# relay_button.net
KiCad netlist of a schematic drawn in Altium Designer
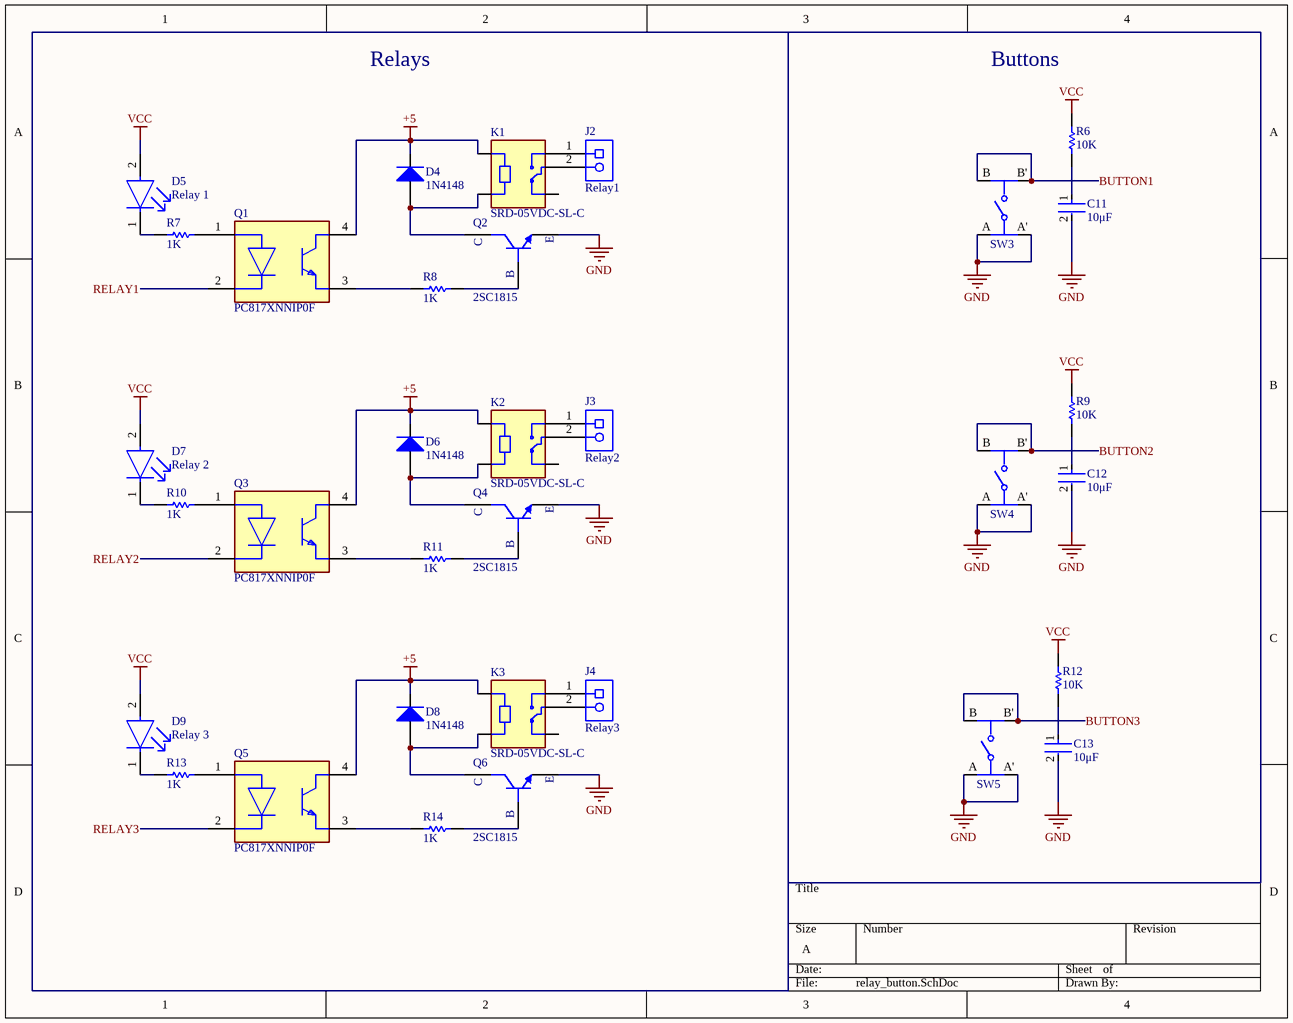
[diagram p0: relay_button.SchDoc]

(export (version "E")
  (design (tool "Eeschema 10.0.6"))
  (components
    (comp (ref "C11")
      (value "10μF")
      (footprint "FP-0603-L_1_6_0_15-W_0_81-IPC_A")
      (description "General Purpose Ceramic Capacitor, 0603, 100nF, 10%, X7R, 15%, 50V")
      (fields (field (name "TOLERANCE") "10%") (field (name "VOLTAGE") "50V"))
      (libsource (lib "Altium Content Vault") (part "02cd4be3c70576c341d710602a673aa"))
    )
    (comp (ref "C12")
      (value "10μF")
      (footprint "FP-0603-L_1_6_0_15-W_0_81-IPC_A")
      (description "General Purpose Ceramic Capacitor, 0603, 100nF, 10%, X7R, 15%, 50V")
      (fields (field (name "TOLERANCE") "10%") (field (name "VOLTAGE") "50V"))
      (libsource (lib "Altium Content Vault") (part "02cd4be3c70576c341d710602a673aa"))
    )
    (comp (ref "C13")
      (value "10μF")
      (footprint "FP-0603-L_1_6_0_15-W_0_81-IPC_A")
      (description "General Purpose Ceramic Capacitor, 0603, 100nF, 10%, X7R, 15%, 50V")
      (fields (field (name "TOLERANCE") "10%") (field (name "VOLTAGE") "50V"))
      (libsource (lib "Altium Content Vault") (part "02cd4be3c70576c341d710602a673aa"))
    )
    (comp (ref "D4")
      (value "1N4148")
      (footprint "NXP-SOD27-2_V")
      (description "High-speed Diode, 100 V, 450 mA, 2-Pin SOD27, RoHS")
      (fields (field (name "MANUFACTURER") "NXP Semiconductors"))
      (libsource (lib "Altium Content Vault") (part "NXP-A1K2-2"))
    )
    (comp (ref "D5")
      (value "Relay 1")
      (footprint "FP-HLMP-4700-MFG")
      (description "LED RED DIFFUSED T-1 3/4 T/H")
      (fields
        (field (name "OCTOPART") "https://octopart.com/hlmp-4700-broadcom-71130526")
        (field (name "MANUFACTURER") "Broadcom")
      )
      (libsource (lib "Altium Content Vault") (part "8706943c75ba83719d021d2fdc84c58"))
    )
    (comp (ref "D6")
      (value "1N4148")
      (footprint "NXP-SOD27-2_V")
      (description "High-speed Diode, 100 V, 450 mA, 2-Pin SOD27, RoHS")
      (fields (field (name "MANUFACTURER") "NXP Semiconductors"))
      (libsource (lib "Altium Content Vault") (part "NXP-A1K2-2"))
    )
    (comp (ref "D7")
      (value "Relay 2")
      (footprint "FP-HLMP-4700-MFG")
      (description "LED RED DIFFUSED T-1 3/4 T/H")
      (fields
        (field (name "OCTOPART") "https://octopart.com/hlmp-4700-broadcom-71130526")
        (field (name "MANUFACTURER") "Broadcom")
      )
      (libsource (lib "Altium Content Vault") (part "8706943c75ba83719d021d2fdc84c58"))
    )
    (comp (ref "D8")
      (value "1N4148")
      (footprint "NXP-SOD27-2_V")
      (description "High-speed Diode, 100 V, 450 mA, 2-Pin SOD27, RoHS")
      (fields (field (name "MANUFACTURER") "NXP Semiconductors"))
      (libsource (lib "Altium Content Vault") (part "NXP-A1K2-2"))
    )
    (comp (ref "D9")
      (value "Relay 3")
      (footprint "FP-HLMP-4700-MFG")
      (description "LED RED DIFFUSED T-1 3/4 T/H")
      (fields
        (field (name "OCTOPART") "https://octopart.com/hlmp-4700-broadcom-71130526")
        (field (name "MANUFACTURER") "Broadcom")
      )
      (libsource (lib "Altium Content Vault") (part "8706943c75ba83719d021d2fdc84c58"))
    )
    (comp (ref "J2")
      (value "Relay1")
      (footprint "PHOE-1729128-2_V")
      (description "PCB Terminal Block, 13.5 A, 400 V, 2-Pin THD, RoHS, Bulk")
      (fields (field (name "PARTNUMBER") "1729128") (field (name "MANUFACTURER") "Phoenix Contact"))
      (libsource (lib "Altium Content Vault") (part "CN-2P-F-R2"))
    )
    (comp (ref "J3")
      (value "Relay2")
      (footprint "PHOE-1729128-2_V")
      (description "PCB Terminal Block, 13.5 A, 400 V, 2-Pin THD, RoHS, Bulk")
      (fields (field (name "PARTNUMBER") "1729128") (field (name "MANUFACTURER") "Phoenix Contact"))
      (libsource (lib "Altium Content Vault") (part "CN-2P-F-R2"))
    )
    (comp (ref "J4")
      (value "Relay3")
      (footprint "PHOE-1729128-2_V")
      (description "PCB Terminal Block, 13.5 A, 400 V, 2-Pin THD, RoHS, Bulk")
      (fields (field (name "PARTNUMBER") "1729128") (field (name "MANUFACTURER") "Phoenix Contact"))
      (libsource (lib "Altium Content Vault") (part "CN-2P-F-R2"))
    )
    (comp (ref "K1")
      (value "SRD-05VDC-SL-C")
      (footprint "RELAY_SRD-05VDC-SL-C")
      (fields (field (name "MF") "{'manufacturer': u'Songle Relay'}"))
      (libsource (lib "SnapEDA_Library") (part "SRD-05VDC-SL-C"))
    )
    (comp (ref "K2")
      (value "SRD-05VDC-SL-C")
      (footprint "RELAY_SRD-05VDC-SL-C")
      (fields (field (name "MF") "{'manufacturer': u'Songle Relay'}"))
      (libsource (lib "SnapEDA_Library") (part "SRD-05VDC-SL-C"))
    )
    (comp (ref "K3")
      (value "SRD-05VDC-SL-C")
      (footprint "RELAY_SRD-05VDC-SL-C")
      (fields (field (name "MF") "{'manufacturer': u'Songle Relay'}"))
      (libsource (lib "SnapEDA_Library") (part "SRD-05VDC-SL-C"))
    )
    (comp (ref "Q1")
      (value "PC817XNNIP0F")
      (footprint "FP-PC817XNNIP0F-MFG")
      (description "OPTOISOLATOR 5KV TRANS 4SMD")
      (libsource (lib "Altium Content Vault") (part "6470904bf6395c62928ee73e60120b8"))
    )
    (comp (ref "Q2")
      (value "2SC1815")
      (footprint "SOT23_3")
      (description "TRANS NPN 50V 0.15A SOT23-3")
      (libsource (lib "BYTECH_HW_LIB_2019") (part "2SC1815"))
    )
    (comp (ref "Q3")
      (value "PC817XNNIP0F")
      (footprint "FP-PC817XNNIP0F-MFG")
      (description "OPTOISOLATOR 5KV TRANS 4SMD")
      (libsource (lib "Altium Content Vault") (part "6470904bf6395c62928ee73e60120b8"))
    )
    (comp (ref "Q4")
      (value "2SC1815")
      (footprint "SOT23_3")
      (description "TRANS NPN 50V 0.15A SOT23-3")
      (libsource (lib "BYTECH_HW_LIB_2019") (part "2SC1815"))
    )
    (comp (ref "Q5")
      (value "PC817XNNIP0F")
      (footprint "FP-PC817XNNIP0F-MFG")
      (description "OPTOISOLATOR 5KV TRANS 4SMD")
      (libsource (lib "Altium Content Vault") (part "6470904bf6395c62928ee73e60120b8"))
    )
    (comp (ref "Q6")
      (value "2SC1815")
      (footprint "SOT23_3")
      (description "TRANS NPN 50V 0.15A SOT23-3")
      (libsource (lib "BYTECH_HW_LIB_2019") (part "2SC1815"))
    )
    (comp (ref "R6")
      (value "10K")
      (footprint "RESC1609X55X30ML15T15")
      (description "Chip Resistor, 10 KOhm, +/- 1%, 0.1 W, -55 to 155 degC, 0603 (1608 Metric), RoHS, Tape and Reel")
      (fields (field (name "TOLERANCE") "1%") (field (name "MANUFACTURER") "Panasonic"))
      (libsource (lib "Altium Content Vault") (part "RES-2"))
    )
    (comp (ref "R7")
      (value "1K")
      (footprint "RESC1609X55X30ML15T15")
      (description "Chip Resistor, 10 KOhm, +/- 1%, 0.1 W, -55 to 155 degC, 0603 (1608 Metric), RoHS, Tape and Reel")
      (fields (field (name "TOLERANCE") "1%") (field (name "MANUFACTURER") "Panasonic"))
      (libsource (lib "Altium Content Vault") (part "RES-2"))
    )
    (comp (ref "R8")
      (value "1K")
      (footprint "RESC1609X55X30ML15T15")
      (description "Chip Resistor, 10 KOhm, +/- 1%, 0.1 W, -55 to 155 degC, 0603 (1608 Metric), RoHS, Tape and Reel")
      (fields (field (name "TOLERANCE") "1%") (field (name "MANUFACTURER") "Panasonic"))
      (libsource (lib "Altium Content Vault") (part "RES-2"))
    )
    (comp (ref "R9")
      (value "10K")
      (footprint "RESC1609X55X30ML15T15")
      (description "Chip Resistor, 10 KOhm, +/- 1%, 0.1 W, -55 to 155 degC, 0603 (1608 Metric), RoHS, Tape and Reel")
      (fields (field (name "TOLERANCE") "1%") (field (name "MANUFACTURER") "Panasonic"))
      (libsource (lib "Altium Content Vault") (part "RES-2"))
    )
    (comp (ref "R10")
      (value "1K")
      (footprint "RESC1609X55X30ML15T15")
      (description "Chip Resistor, 10 KOhm, +/- 1%, 0.1 W, -55 to 155 degC, 0603 (1608 Metric), RoHS, Tape and Reel")
      (fields (field (name "TOLERANCE") "1%") (field (name "MANUFACTURER") "Panasonic"))
      (libsource (lib "Altium Content Vault") (part "RES-2"))
    )
    (comp (ref "R11")
      (value "1K")
      (footprint "RESC1609X55X30ML15T15")
      (description "Chip Resistor, 10 KOhm, +/- 1%, 0.1 W, -55 to 155 degC, 0603 (1608 Metric), RoHS, Tape and Reel")
      (fields (field (name "TOLERANCE") "1%") (field (name "MANUFACTURER") "Panasonic"))
      (libsource (lib "Altium Content Vault") (part "RES-2"))
    )
    (comp (ref "R12")
      (value "10K")
      (footprint "RESC1609X55X30ML15T15")
      (description "Chip Resistor, 10 KOhm, +/- 1%, 0.1 W, -55 to 155 degC, 0603 (1608 Metric), RoHS, Tape and Reel")
      (fields (field (name "TOLERANCE") "1%") (field (name "MANUFACTURER") "Panasonic"))
      (libsource (lib "Altium Content Vault") (part "RES-2"))
    )
    (comp (ref "R13")
      (value "1K")
      (footprint "RESC1609X55X30ML15T15")
      (description "Chip Resistor, 10 KOhm, +/- 1%, 0.1 W, -55 to 155 degC, 0603 (1608 Metric), RoHS, Tape and Reel")
      (fields (field (name "TOLERANCE") "1%") (field (name "MANUFACTURER") "Panasonic"))
      (libsource (lib "Altium Content Vault") (part "RES-2"))
    )
    (comp (ref "R14")
      (value "1K")
      (footprint "RESC1609X55X30ML15T15")
      (description "Chip Resistor, 10 KOhm, +/- 1%, 0.1 W, -55 to 155 degC, 0603 (1608 Metric), RoHS, Tape and Reel")
      (fields (field (name "TOLERANCE") "1%") (field (name "MANUFACTURER") "Panasonic"))
      (libsource (lib "Altium Content Vault") (part "RES-2"))
    )
    (comp (ref "SW3")
      (value "RESET")
      (footprint "FP-EVQ-PAG05R-MFG")
      (description "SWITCH TACTILE SPST-NO 0.02A 15V")
      (libsource (lib "Altium Content Vault") (part "841f23923f71b23f3ea0ab5dfb78dcc"))
    )
    (comp (ref "SW4")
      (value "RESET")
      (footprint "FP-EVQ-PAG05R-MFG")
      (description "SWITCH TACTILE SPST-NO 0.02A 15V")
      (libsource (lib "Altium Content Vault") (part "841f23923f71b23f3ea0ab5dfb78dcc"))
    )
    (comp (ref "SW5")
      (value "RESET")
      (footprint "FP-EVQ-PAG05R-MFG")
      (description "SWITCH TACTILE SPST-NO 0.02A 15V")
      (libsource (lib "Altium Content Vault") (part "841f23923f71b23f3ea0ab5dfb78dcc"))
    )
  )
  (nets
    (net (code "1") (name "+5") (class "Default")
      (node (ref "D4") (pin "2") (pinfunction "K_2") (pintype "passive"))
      (node (ref "D6") (pin "2") (pinfunction "K_2") (pintype "passive"))
      (node (ref "D8") (pin "2") (pinfunction "K_2") (pintype "passive"))
      (node (ref "K1") (pin "A1") (pinfunction "A1_A1") (pintype "passive"))
      (node (ref "K2") (pin "A1") (pinfunction "A1_A1") (pintype "passive"))
      (node (ref "K3") (pin "A1") (pinfunction "A1_A1") (pintype "passive"))
      (node (ref "Q1") (pin "4") (pinfunction "C_4") (pintype "passive"))
      (node (ref "Q3") (pin "4") (pinfunction "C_4") (pintype "passive"))
      (node (ref "Q5") (pin "4") (pinfunction "C_4") (pintype "passive"))
    )
    (net (code "2") (name "/BUTTON1") (class "Default")
      (node (ref "SW3") (pin "B") (pinfunction "B_B") (pintype "passive"))
      (node (ref "SW3") (pin "B'") (pinfunction "B'_B'") (pintype "passive"))
    )
    (net (code "3") (name "/BUTTON2") (class "Default")
      (node (ref "SW4") (pin "B") (pinfunction "B_B") (pintype "passive"))
      (node (ref "SW4") (pin "B'") (pinfunction "B'_B'") (pintype "passive"))
    )
    (net (code "4") (name "/BUTTON3") (class "Default")
      (node (ref "SW5") (pin "B") (pinfunction "B_B") (pintype "passive"))
      (node (ref "SW5") (pin "B'") (pinfunction "B'_B'") (pintype "passive"))
    )
    (net (code "5") (name "/RELAY1") (class "Default")
      (node (ref "Q1") (pin "2") (pinfunction "C_2") (pintype "passive"))
    )
    (net (code "6") (name "/RELAY2") (class "Default")
      (node (ref "Q3") (pin "2") (pinfunction "C_2") (pintype "passive"))
    )
    (net (code "7") (name "/RELAY3") (class "Default")
      (node (ref "Q5") (pin "2") (pinfunction "C_2") (pintype "passive"))
    )
    (net (code "8") (name "GND") (class "Default")
      (node (ref "C11") (pin "2") (pinfunction "2_2") (pintype "passive"))
      (node (ref "C12") (pin "2") (pinfunction "2_2") (pintype "passive"))
      (node (ref "C13") (pin "2") (pinfunction "2_2") (pintype "passive"))
      (node (ref "Q2") (pin "2") (pinfunction "E_2") (pintype "passive"))
      (node (ref "Q4") (pin "2") (pinfunction "E_2") (pintype "passive"))
      (node (ref "Q6") (pin "2") (pinfunction "E_2") (pintype "passive"))
      (node (ref "SW3") (pin "A") (pinfunction "A_A") (pintype "passive"))
      (node (ref "SW3") (pin "A'") (pinfunction "A'_A'") (pintype "passive"))
      (node (ref "SW4") (pin "A") (pinfunction "A_A") (pintype "passive"))
      (node (ref "SW4") (pin "A'") (pinfunction "A'_A'") (pintype "passive"))
      (node (ref "SW5") (pin "A") (pinfunction "A_A") (pintype "passive"))
      (node (ref "SW5") (pin "A'") (pinfunction "A'_A'") (pintype "passive"))
    )
    (net (code "9") (name "Net-(C11-Pad1)") (class "Default")
      (node (ref "C11") (pin "1") (pinfunction "1_1") (pintype "passive"))
      (node (ref "R6") (pin "1") (pinfunction "1_1") (pintype "passive"))
    )
    (net (code "10") (name "Net-(C12-Pad1)") (class "Default")
      (node (ref "C12") (pin "1") (pinfunction "1_1") (pintype "passive"))
      (node (ref "R9") (pin "1") (pinfunction "1_1") (pintype "passive"))
    )
    (net (code "11") (name "Net-(C13-Pad1)") (class "Default")
      (node (ref "C13") (pin "1") (pinfunction "1_1") (pintype "passive"))
      (node (ref "R12") (pin "1") (pinfunction "1_1") (pintype "passive"))
    )
    (net (code "12") (name "Net-(D4-A)") (class "Default")
      (node (ref "D4") (pin "1") (pinfunction "A_1") (pintype "passive"))
      (node (ref "K1") (pin "A2") (pinfunction "A2_A2") (pintype "passive"))
      (node (ref "Q2") (pin "3") (pinfunction "C_3") (pintype "passive"))
    )
    (net (code "13") (name "Net-(D5-C)") (class "Default")
      (node (ref "D5") (pin "1") (pinfunction "C_1") (pintype "passive"))
      (node (ref "R7") (pin "1") (pinfunction "1_1") (pintype "passive"))
    )
    (net (code "14") (name "Net-(D6-A)") (class "Default")
      (node (ref "D6") (pin "1") (pinfunction "A_1") (pintype "passive"))
      (node (ref "K2") (pin "A2") (pinfunction "A2_A2") (pintype "passive"))
      (node (ref "Q4") (pin "3") (pinfunction "C_3") (pintype "passive"))
    )
    (net (code "15") (name "Net-(D7-C)") (class "Default")
      (node (ref "D7") (pin "1") (pinfunction "C_1") (pintype "passive"))
      (node (ref "R10") (pin "1") (pinfunction "1_1") (pintype "passive"))
    )
    (net (code "16") (name "Net-(D8-A)") (class "Default")
      (node (ref "D8") (pin "1") (pinfunction "A_1") (pintype "passive"))
      (node (ref "K3") (pin "A2") (pinfunction "A2_A2") (pintype "passive"))
      (node (ref "Q6") (pin "3") (pinfunction "C_3") (pintype "passive"))
    )
    (net (code "17") (name "Net-(D9-C)") (class "Default")
      (node (ref "D9") (pin "1") (pinfunction "C_1") (pintype "passive"))
      (node (ref "R13") (pin "1") (pinfunction "1_1") (pintype "passive"))
    )
    (net (code "18") (name "Net-(J2-Pad1)") (class "Default")
      (node (ref "J2") (pin "1") (pinfunction "1_1") (pintype "passive"))
      (node (ref "K1") (pin "NO") (pinfunction "NO_NO") (pintype "passive"))
    )
    (net (code "19") (name "Net-(J2-Pad2)") (class "Default")
      (node (ref "J2") (pin "2") (pinfunction "2_2") (pintype "passive"))
      (node (ref "K1") (pin "COM") (pinfunction "COM_COM") (pintype "passive"))
    )
    (net (code "20") (name "Net-(J3-Pad1)") (class "Default")
      (node (ref "J3") (pin "1") (pinfunction "1_1") (pintype "passive"))
      (node (ref "K2") (pin "NO") (pinfunction "NO_NO") (pintype "passive"))
    )
    (net (code "21") (name "Net-(J3-Pad2)") (class "Default")
      (node (ref "J3") (pin "2") (pinfunction "2_2") (pintype "passive"))
      (node (ref "K2") (pin "COM") (pinfunction "COM_COM") (pintype "passive"))
    )
    (net (code "22") (name "Net-(J4-Pad1)") (class "Default")
      (node (ref "J4") (pin "1") (pinfunction "1_1") (pintype "passive"))
      (node (ref "K3") (pin "NO") (pinfunction "NO_NO") (pintype "passive"))
    )
    (net (code "23") (name "Net-(J4-Pad2)") (class "Default")
      (node (ref "J4") (pin "2") (pinfunction "2_2") (pintype "passive"))
      (node (ref "K3") (pin "COM") (pinfunction "COM_COM") (pintype "passive"))
    )
    (net (code "24") (name "Net-(Q1-A)") (class "Default")
      (node (ref "Q1") (pin "1") (pinfunction "A_1") (pintype "passive"))
      (node (ref "R7") (pin "2") (pinfunction "2_2") (pintype "passive"))
    )
    (net (code "25") (name "Net-(Q1-E)") (class "Default")
      (node (ref "Q1") (pin "3") (pinfunction "E_3") (pintype "passive"))
      (node (ref "R8") (pin "1") (pinfunction "1_1") (pintype "passive"))
    )
    (net (code "26") (name "Net-(Q2-B)") (class "Default")
      (node (ref "Q2") (pin "1") (pinfunction "B_1") (pintype "passive"))
      (node (ref "R8") (pin "2") (pinfunction "2_2") (pintype "passive"))
    )
    (net (code "27") (name "Net-(Q3-A)") (class "Default")
      (node (ref "Q3") (pin "1") (pinfunction "A_1") (pintype "passive"))
      (node (ref "R10") (pin "2") (pinfunction "2_2") (pintype "passive"))
    )
    (net (code "28") (name "Net-(Q3-E)") (class "Default")
      (node (ref "Q3") (pin "3") (pinfunction "E_3") (pintype "passive"))
      (node (ref "R11") (pin "1") (pinfunction "1_1") (pintype "passive"))
    )
    (net (code "29") (name "Net-(Q4-B)") (class "Default")
      (node (ref "Q4") (pin "1") (pinfunction "B_1") (pintype "passive"))
      (node (ref "R11") (pin "2") (pinfunction "2_2") (pintype "passive"))
    )
    (net (code "30") (name "Net-(Q5-A)") (class "Default")
      (node (ref "Q5") (pin "1") (pinfunction "A_1") (pintype "passive"))
      (node (ref "R13") (pin "2") (pinfunction "2_2") (pintype "passive"))
    )
    (net (code "31") (name "Net-(Q5-E)") (class "Default")
      (node (ref "Q5") (pin "3") (pinfunction "E_3") (pintype "passive"))
      (node (ref "R14") (pin "1") (pinfunction "1_1") (pintype "passive"))
    )
    (net (code "32") (name "Net-(Q6-B)") (class "Default")
      (node (ref "Q6") (pin "1") (pinfunction "B_1") (pintype "passive"))
      (node (ref "R14") (pin "2") (pinfunction "2_2") (pintype "passive"))
    )
    (net (code "33") (name "VCC") (class "Default")
      (node (ref "D5") (pin "2") (pinfunction "A_2") (pintype "passive"))
      (node (ref "D7") (pin "2") (pinfunction "A_2") (pintype "passive"))
      (node (ref "D9") (pin "2") (pinfunction "A_2") (pintype "passive"))
      (node (ref "R12") (pin "2") (pinfunction "2_2") (pintype "passive"))
      (node (ref "R6") (pin "2") (pinfunction "2_2") (pintype "passive"))
      (node (ref "R9") (pin "2") (pinfunction "2_2") (pintype "passive"))
    )
    (net (code "34") (name "unconnected-(K1-PadNC)") (class "Default")
      (node (ref "K1") (pin "NC") (pinfunction "NC_NC") (pintype "passive"))
    )
    (net (code "35") (name "unconnected-(K2-PadNC)") (class "Default")
      (node (ref "K2") (pin "NC") (pinfunction "NC_NC") (pintype "passive"))
    )
    (net (code "36") (name "unconnected-(K3-PadNC)") (class "Default")
      (node (ref "K3") (pin "NC") (pinfunction "NC_NC") (pintype "passive"))
    )
  )
)
